# SECSENSE.net
KiCad netlist of a schematic drawn in EAGLE
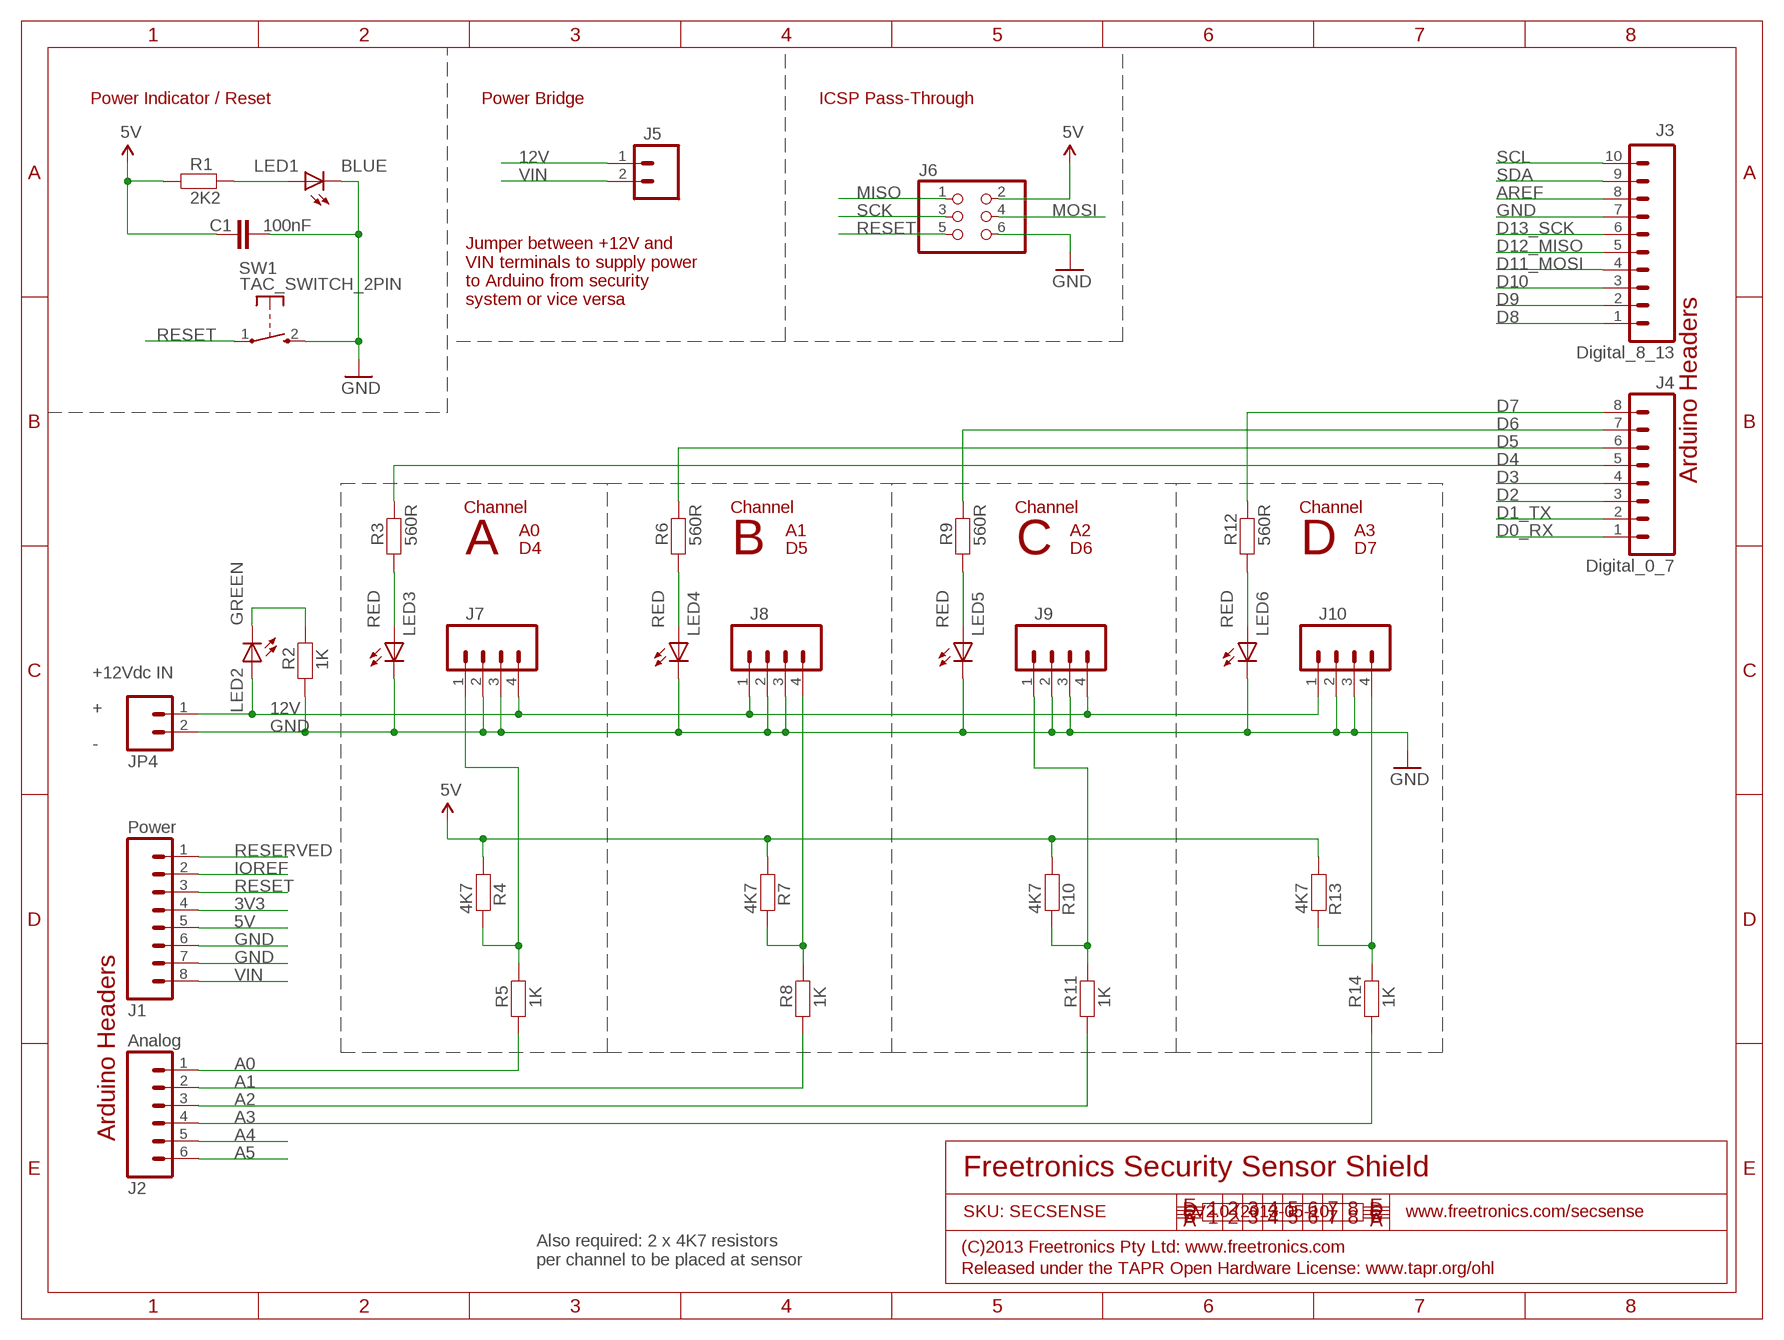
[diagram p0: schematic, sheet 1]

(export (version "E")
  (design (tool "Eeschema 10.0.6"))
  (components
    (comp (ref "C1")
      (value "100nF")
      (footprint "eagle-import:0603")
      (libsource (lib "eagle-import") (part "CAP0603"))
    )
    (comp (ref "J1")
      (value "Power")
      (footprint "eagle-import:1X08")
      (libsource (lib "eagle-import") (part "M08"))
    )
    (comp (ref "J2")
      (value "Analog")
      (footprint "eagle-import:1X06")
      (libsource (lib "eagle-import") (part "M06SIP"))
    )
    (comp (ref "J3")
      (value "Digital_8_13")
      (footprint "eagle-import:1X10")
      (libsource (lib "eagle-import") (part "M100.1"))
    )
    (comp (ref "J4")
      (value "Digital_0_7")
      (footprint "eagle-import:1X08")
      (libsource (lib "eagle-import") (part "M08"))
    )
    (comp (ref "J5")
      (value "M02PTH")
      (footprint "eagle-import:1X02")
      (libsource (lib "eagle-import") (part "freetronics-original_M02PTH"))
    )
    (comp (ref "J6")
      (value "PINHD-2X3")
      (footprint "eagle-import:2X03")
      (libsource (lib "eagle-import") (part "PINHD-2X3"))
    )
    (comp (ref "J7")
      (value "M04SCREW")
      (footprint "eagle-import:SCREWTERMINAL-3.5MM-4")
      (libsource (lib "eagle-import") (part "M04SCREW"))
    )
    (comp (ref "J8")
      (value "M04SCREW")
      (footprint "eagle-import:SCREWTERMINAL-3.5MM-4")
      (libsource (lib "eagle-import") (part "M04SCREW"))
    )
    (comp (ref "J9")
      (value "M04SCREW")
      (footprint "eagle-import:SCREWTERMINAL-3.5MM-4")
      (libsource (lib "eagle-import") (part "M04SCREW"))
    )
    (comp (ref "J10")
      (value "M04SCREW")
      (footprint "eagle-import:SCREWTERMINAL-3.5MM-4")
      (libsource (lib "eagle-import") (part "M04SCREW"))
    )
    (comp (ref "JP4")
      (value "M023.5MM")
      (footprint "eagle-import:SCREWTERMINAL-3.5MM-2")
      (libsource (lib "eagle-import") (part "M023.5MM"))
    )
    (comp (ref "LED1")
      (value "BLUE")
      (footprint "eagle-import:LED-0603")
      (libsource (lib "eagle-import") (part "LED0603"))
    )
    (comp (ref "LED2")
      (value "GREEN")
      (footprint "eagle-import:LED-0603")
      (libsource (lib "eagle-import") (part "LED0603"))
    )
    (comp (ref "LED3")
      (value "RED")
      (footprint "eagle-import:LED-0603")
      (libsource (lib "eagle-import") (part "LED0603"))
    )
    (comp (ref "LED4")
      (value "RED")
      (footprint "eagle-import:LED-0603")
      (libsource (lib "eagle-import") (part "LED0603"))
    )
    (comp (ref "LED5")
      (value "RED")
      (footprint "eagle-import:LED-0603")
      (libsource (lib "eagle-import") (part "LED0603"))
    )
    (comp (ref "LED6")
      (value "RED")
      (footprint "eagle-import:LED-0603")
      (libsource (lib "eagle-import") (part "LED0603"))
    )
    (comp (ref "R1")
      (value "2K2")
      (footprint "eagle-import:0603")
      (libsource (lib "eagle-import") (part "RESISTOR0603"))
    )
    (comp (ref "R2")
      (value "1K")
      (footprint "eagle-import:0603")
      (libsource (lib "eagle-import") (part "RESISTOR0603"))
    )
    (comp (ref "R3")
      (value "560R")
      (footprint "eagle-import:0603")
      (libsource (lib "eagle-import") (part "RESISTOR0603"))
    )
    (comp (ref "R4")
      (value "4K7")
      (footprint "eagle-import:0603")
      (libsource (lib "eagle-import") (part "RESISTOR0603"))
    )
    (comp (ref "R5")
      (value "1K")
      (footprint "eagle-import:0603")
      (libsource (lib "eagle-import") (part "RESISTOR0603"))
    )
    (comp (ref "R6")
      (value "560R")
      (footprint "eagle-import:0603")
      (libsource (lib "eagle-import") (part "RESISTOR0603"))
    )
    (comp (ref "R7")
      (value "4K7")
      (footprint "eagle-import:0603")
      (libsource (lib "eagle-import") (part "RESISTOR0603"))
    )
    (comp (ref "R8")
      (value "1K")
      (footprint "eagle-import:0603")
      (libsource (lib "eagle-import") (part "RESISTOR0603"))
    )
    (comp (ref "R9")
      (value "560R")
      (footprint "eagle-import:0603")
      (libsource (lib "eagle-import") (part "RESISTOR0603"))
    )
    (comp (ref "R10")
      (value "4K7")
      (footprint "eagle-import:0603")
      (libsource (lib "eagle-import") (part "RESISTOR0603"))
    )
    (comp (ref "R11")
      (value "1K")
      (footprint "eagle-import:0603")
      (libsource (lib "eagle-import") (part "RESISTOR0603"))
    )
    (comp (ref "R12")
      (value "560R")
      (footprint "eagle-import:0603")
      (libsource (lib "eagle-import") (part "RESISTOR0603"))
    )
    (comp (ref "R13")
      (value "4K7")
      (footprint "eagle-import:0603")
      (libsource (lib "eagle-import") (part "RESISTOR0603"))
    )
    (comp (ref "R14")
      (value "1K")
      (footprint "eagle-import:0603")
      (libsource (lib "eagle-import") (part "RESISTOR0603"))
    )
    (comp (ref "SW1")
      (value "TAC_SWITCH_2PIN")
      (footprint "eagle-import:TACTILE_SWITCH_SMD_2PIN_TINY")
      (libsource (lib "eagle-import") (part "TAC_SWITCH_2PIN"))
    )
  )
  (nets
    (net (code "1") (name "/3V3") (class "Default")
      (node (ref "J1") (pin "4") (pinfunction "4_4") (pintype "passive"))
    )
    (net (code "2") (name "/12V") (class "Default")
      (node (ref "J10") (pin "1") (pinfunction "1_1") (pintype "passive"))
      (node (ref "J5") (pin "1") (pinfunction "1_1") (pintype "passive"))
      (node (ref "J7") (pin "4") (pinfunction "4_4") (pintype "passive"))
      (node (ref "J8") (pin "1") (pinfunction "1_1") (pintype "passive"))
      (node (ref "J9") (pin "4") (pinfunction "4_4") (pintype "passive"))
      (node (ref "JP4") (pin "1") (pinfunction "1_1") (pintype "passive"))
      (node (ref "LED2") (pin "A") (pinfunction "A_A") (pintype "passive"))
    )
    (net (code "3") (name "/A0") (class "Default")
      (node (ref "J2") (pin "1") (pinfunction "1_1") (pintype "passive"))
      (node (ref "R5") (pin "1") (pinfunction "1_1") (pintype "passive"))
    )
    (net (code "4") (name "/A1") (class "Default")
      (node (ref "J2") (pin "2") (pinfunction "2_2") (pintype "passive"))
      (node (ref "R8") (pin "1") (pinfunction "1_1") (pintype "passive"))
    )
    (net (code "5") (name "/A2") (class "Default")
      (node (ref "J2") (pin "3") (pinfunction "3_3") (pintype "passive"))
      (node (ref "R11") (pin "1") (pinfunction "1_1") (pintype "passive"))
    )
    (net (code "6") (name "/A3") (class "Default")
      (node (ref "J2") (pin "4") (pinfunction "4_4") (pintype "passive"))
      (node (ref "R14") (pin "1") (pinfunction "1_1") (pintype "passive"))
    )
    (net (code "7") (name "/A4") (class "Default")
      (node (ref "J2") (pin "5") (pinfunction "5_5") (pintype "passive"))
    )
    (net (code "8") (name "/A5") (class "Default")
      (node (ref "J2") (pin "6") (pinfunction "6_6") (pintype "passive"))
    )
    (net (code "9") (name "/AREF") (class "Default")
      (node (ref "J3") (pin "8") (pinfunction "8_8") (pintype "passive"))
    )
    (net (code "10") (name "/D0_RX") (class "Default")
      (node (ref "J4") (pin "1") (pinfunction "1_1") (pintype "passive"))
    )
    (net (code "11") (name "/D1_TX") (class "Default")
      (node (ref "J4") (pin "2") (pinfunction "2_2") (pintype "passive"))
    )
    (net (code "12") (name "/D2") (class "Default")
      (node (ref "J4") (pin "3") (pinfunction "3_3") (pintype "passive"))
    )
    (net (code "13") (name "/D3") (class "Default")
      (node (ref "J4") (pin "4") (pinfunction "4_4") (pintype "passive"))
    )
    (net (code "14") (name "/D4") (class "Default")
      (node (ref "J4") (pin "5") (pinfunction "5_5") (pintype "passive"))
      (node (ref "R3") (pin "2") (pinfunction "2_2") (pintype "passive"))
    )
    (net (code "15") (name "/D5") (class "Default")
      (node (ref "J4") (pin "6") (pinfunction "6_6") (pintype "passive"))
      (node (ref "R6") (pin "2") (pinfunction "2_2") (pintype "passive"))
    )
    (net (code "16") (name "/D6") (class "Default")
      (node (ref "J4") (pin "7") (pinfunction "7_7") (pintype "passive"))
      (node (ref "R9") (pin "2") (pinfunction "2_2") (pintype "passive"))
    )
    (net (code "17") (name "/D7") (class "Default")
      (node (ref "J4") (pin "8") (pinfunction "8_8") (pintype "passive"))
      (node (ref "R12") (pin "2") (pinfunction "2_2") (pintype "passive"))
    )
    (net (code "18") (name "/D8") (class "Default")
      (node (ref "J3") (pin "1") (pinfunction "1_1") (pintype "passive"))
    )
    (net (code "19") (name "/D9") (class "Default")
      (node (ref "J3") (pin "2") (pinfunction "2_2") (pintype "passive"))
    )
    (net (code "20") (name "/D10") (class "Default")
      (node (ref "J3") (pin "3") (pinfunction "3_3") (pintype "passive"))
    )
    (net (code "21") (name "/D11_MOSI") (class "Default")
      (node (ref "J3") (pin "4") (pinfunction "4_4") (pintype "passive"))
    )
    (net (code "22") (name "/D12_MISO") (class "Default")
      (node (ref "J3") (pin "5") (pinfunction "5_5") (pintype "passive"))
    )
    (net (code "23") (name "/D13_SCK") (class "Default")
      (node (ref "J3") (pin "6") (pinfunction "6_6") (pintype "passive"))
    )
    (net (code "24") (name "/IOREF") (class "Default")
      (node (ref "J1") (pin "2") (pinfunction "2_2") (pintype "passive"))
    )
    (net (code "25") (name "/MISO") (class "Default")
      (node (ref "J6") (pin "1") (pinfunction "1_1") (pintype "passive"))
    )
    (net (code "26") (name "/MOSI") (class "Default")
      (node (ref "J6") (pin "4") (pinfunction "4_4") (pintype "passive"))
    )
    (net (code "27") (name "/RESERVED") (class "Default")
      (node (ref "J1") (pin "1") (pinfunction "1_1") (pintype "passive"))
    )
    (net (code "28") (name "/RESET") (class "Default")
      (node (ref "J1") (pin "3") (pinfunction "3_3") (pintype "passive"))
      (node (ref "J6") (pin "5") (pinfunction "5_5") (pintype "passive"))
      (node (ref "SW1") (pin "1") (pinfunction "P_1") (pintype "passive"))
    )
    (net (code "29") (name "/SCK") (class "Default")
      (node (ref "J6") (pin "3") (pinfunction "3_3") (pintype "passive"))
    )
    (net (code "30") (name "/SCL") (class "Default")
      (node (ref "J3") (pin "10") (pinfunction "10_10") (pintype "passive"))
    )
    (net (code "31") (name "/SDA") (class "Default")
      (node (ref "J3") (pin "9") (pinfunction "9_9") (pintype "passive"))
    )
    (net (code "32") (name "/VIN") (class "Default")
      (node (ref "J1") (pin "8") (pinfunction "8_8") (pintype "passive"))
      (node (ref "J5") (pin "2") (pinfunction "2_2") (pintype "passive"))
    )
    (net (code "33") (name "5V") (class "Default")
      (node (ref "C1") (pin "1") (pinfunction "1_1") (pintype "passive"))
      (node (ref "J1") (pin "5") (pinfunction "5_5") (pintype "passive"))
      (node (ref "J6") (pin "2") (pinfunction "2_2") (pintype "passive"))
      (node (ref "R1") (pin "1") (pinfunction "1_1") (pintype "passive"))
      (node (ref "R10") (pin "1") (pinfunction "1_1") (pintype "passive"))
      (node (ref "R13") (pin "1") (pinfunction "1_1") (pintype "passive"))
      (node (ref "R4") (pin "1") (pinfunction "1_1") (pintype "passive"))
      (node (ref "R7") (pin "1") (pinfunction "1_1") (pintype "passive"))
    )
    (net (code "34") (name "GND") (class "Default")
      (node (ref "C1") (pin "2") (pinfunction "2_2") (pintype "passive"))
      (node (ref "J1") (pin "6") (pinfunction "6_6") (pintype "passive"))
      (node (ref "J1") (pin "7") (pinfunction "7_7") (pintype "passive"))
      (node (ref "J10") (pin "2") (pinfunction "2_2") (pintype "passive"))
      (node (ref "J10") (pin "3") (pinfunction "3_3") (pintype "passive"))
      (node (ref "J3") (pin "7") (pinfunction "7_7") (pintype "passive"))
      (node (ref "J6") (pin "6") (pinfunction "6_6") (pintype "passive"))
      (node (ref "J7") (pin "2") (pinfunction "2_2") (pintype "passive"))
      (node (ref "J7") (pin "3") (pinfunction "3_3") (pintype "passive"))
      (node (ref "J8") (pin "2") (pinfunction "2_2") (pintype "passive"))
      (node (ref "J8") (pin "3") (pinfunction "3_3") (pintype "passive"))
      (node (ref "J9") (pin "2") (pinfunction "2_2") (pintype "passive"))
      (node (ref "J9") (pin "3") (pinfunction "3_3") (pintype "passive"))
      (node (ref "JP4") (pin "2") (pinfunction "2_2") (pintype "passive"))
      (node (ref "LED1") (pin "C") (pinfunction "C_C") (pintype "passive"))
      (node (ref "LED3") (pin "C") (pinfunction "C_C") (pintype "passive"))
      (node (ref "LED4") (pin "C") (pinfunction "C_C") (pintype "passive"))
      (node (ref "LED5") (pin "C") (pinfunction "C_C") (pintype "passive"))
      (node (ref "LED6") (pin "C") (pinfunction "C_C") (pintype "passive"))
      (node (ref "R2") (pin "1") (pinfunction "1_1") (pintype "passive"))
      (node (ref "SW1") (pin "2") (pinfunction "S_2") (pintype "passive"))
    )
    (net (code "35") (name "Net-(J7-Pad1)") (class "Default")
      (node (ref "J7") (pin "1") (pinfunction "1_1") (pintype "passive"))
      (node (ref "R4") (pin "2") (pinfunction "2_2") (pintype "passive"))
      (node (ref "R5") (pin "2") (pinfunction "2_2") (pintype "passive"))
    )
    (net (code "36") (name "Net-(J8-Pad4)") (class "Default")
      (node (ref "J8") (pin "4") (pinfunction "4_4") (pintype "passive"))
      (node (ref "R7") (pin "2") (pinfunction "2_2") (pintype "passive"))
      (node (ref "R8") (pin "2") (pinfunction "2_2") (pintype "passive"))
    )
    (net (code "37") (name "Net-(J9-Pad1)") (class "Default")
      (node (ref "J9") (pin "1") (pinfunction "1_1") (pintype "passive"))
      (node (ref "R10") (pin "2") (pinfunction "2_2") (pintype "passive"))
      (node (ref "R11") (pin "2") (pinfunction "2_2") (pintype "passive"))
    )
    (net (code "38") (name "Net-(J10-Pad4)") (class "Default")
      (node (ref "J10") (pin "4") (pinfunction "4_4") (pintype "passive"))
      (node (ref "R13") (pin "2") (pinfunction "2_2") (pintype "passive"))
      (node (ref "R14") (pin "2") (pinfunction "2_2") (pintype "passive"))
    )
    (net (code "39") (name "Net-(LED1-PadA)") (class "Default")
      (node (ref "LED1") (pin "A") (pinfunction "A_A") (pintype "passive"))
      (node (ref "R1") (pin "2") (pinfunction "2_2") (pintype "passive"))
    )
    (net (code "40") (name "Net-(LED2-PadC)") (class "Default")
      (node (ref "LED2") (pin "C") (pinfunction "C_C") (pintype "passive"))
      (node (ref "R2") (pin "2") (pinfunction "2_2") (pintype "passive"))
    )
    (net (code "41") (name "Net-(LED3-PadA)") (class "Default")
      (node (ref "LED3") (pin "A") (pinfunction "A_A") (pintype "passive"))
      (node (ref "R3") (pin "1") (pinfunction "1_1") (pintype "passive"))
    )
    (net (code "42") (name "Net-(LED4-PadA)") (class "Default")
      (node (ref "LED4") (pin "A") (pinfunction "A_A") (pintype "passive"))
      (node (ref "R6") (pin "1") (pinfunction "1_1") (pintype "passive"))
    )
    (net (code "43") (name "Net-(LED5-PadA)") (class "Default")
      (node (ref "LED5") (pin "A") (pinfunction "A_A") (pintype "passive"))
      (node (ref "R9") (pin "1") (pinfunction "1_1") (pintype "passive"))
    )
    (net (code "44") (name "Net-(LED6-PadA)") (class "Default")
      (node (ref "LED6") (pin "A") (pinfunction "A_A") (pintype "passive"))
      (node (ref "R12") (pin "1") (pinfunction "1_1") (pintype "passive"))
    )
  )
)
